# KX1_DB_PWR.net
KiCad netlist of a schematic drawn in Altium Designer
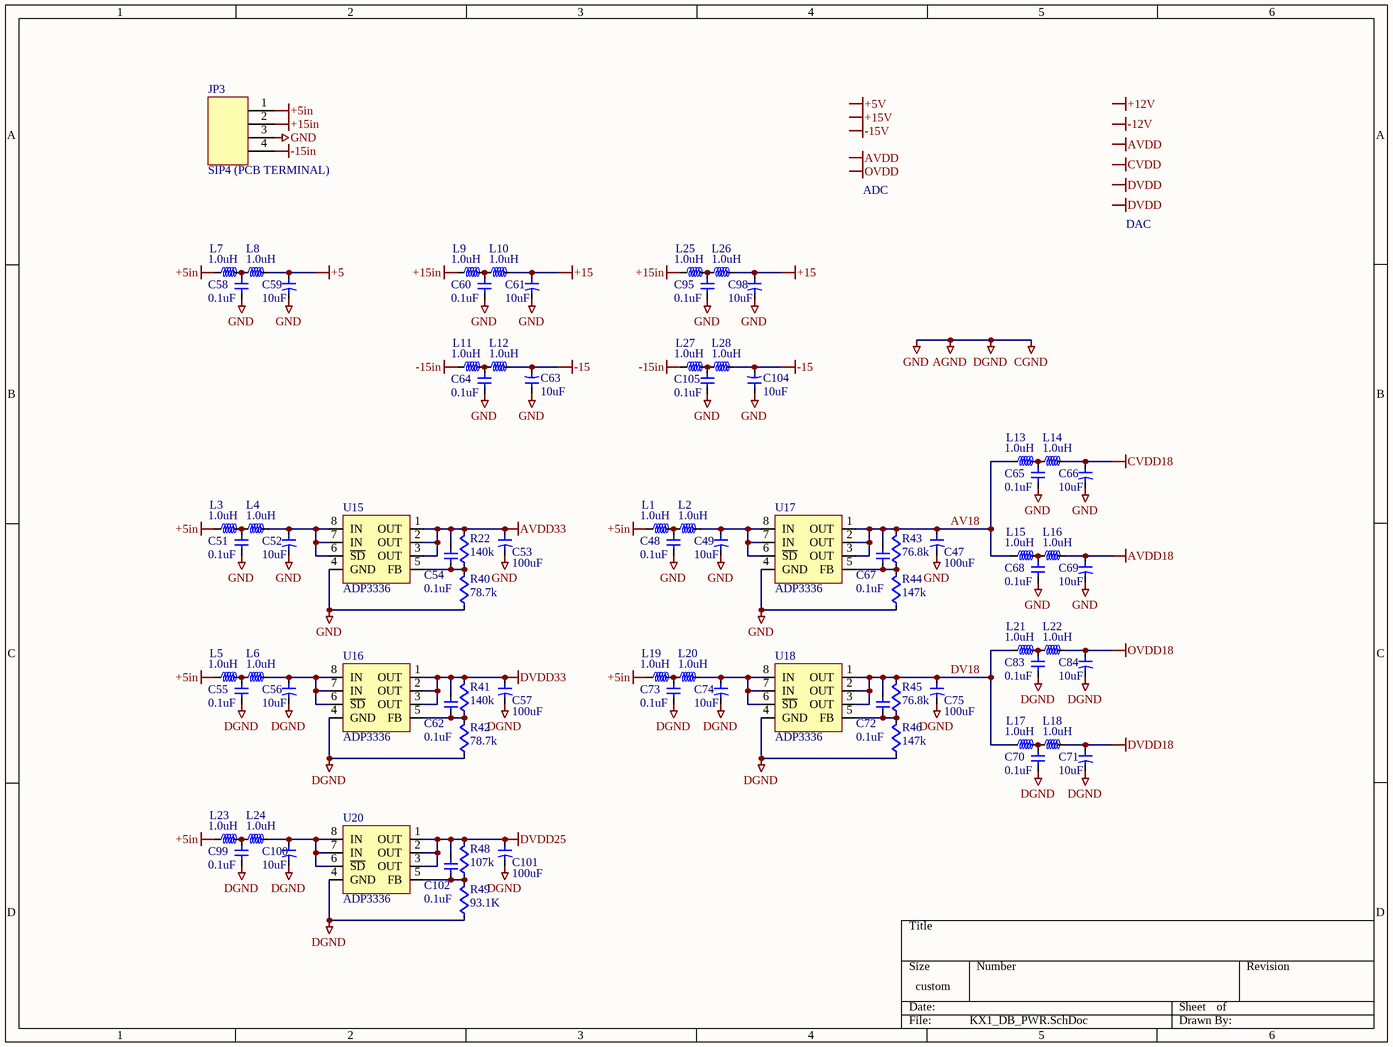
[diagram p0: KX1_DB_PWR.SchDoc]

(export (version "E")
  (design (tool "Eeschema 10.0.6"))
  (components
    (comp (ref "C47")
      (value "100uF")
      (footprint "1206")
      (description "capacitor")
      (fields
        (field (name "MANUFACTURER") "TDK Corporation")
        (field (name "MANUFACTURER PART NUMBER") "C3216X5R0J107M")
      )
      (libsource (lib "KX1_DB") (part "CAPACITOR_SM"))
    )
    (comp (ref "C48")
      (value "0.1uF")
      (footprint "0603w")
      (description "capacitor")
      (fields
        (field (name "MANUFACTURER") "Kemet")
        (field (name "MANUFACTURER PART NUMBER") "C0603C104K3RACTU")
      )
      (libsource (lib "KX1_DB") (part "CAP_SM"))
    )
    (comp (ref "C49")
      (value "10uF")
      (footprint "1206")
      (description "ELECTROLYTIC capacitor")
      (fields
        (field (name "MANUFACTURER") "Nichicon")
        (field (name "MANUFACTURER PART NUMBER") "F971C106MAA")
      )
      (libsource (lib "KX1_DB") (part "CAPACITOR_SM"))
    )
    (comp (ref "C51")
      (value "0.1uF")
      (footprint "0603w")
      (description "capacitor")
      (fields
        (field (name "MANUFACTURER") "Kemet")
        (field (name "MANUFACTURER PART NUMBER") "C0603C104K3RACTU")
      )
      (libsource (lib "KX1_DB") (part "CAP_SM"))
    )
    (comp (ref "C52")
      (value "10uF")
      (footprint "1206")
      (description "ELECTROLYTIC capacitor")
      (fields
        (field (name "MANUFACTURER") "Nichicon")
        (field (name "MANUFACTURER PART NUMBER") "F971C106MAA")
      )
      (libsource (lib "KX1_DB") (part "CAPACITOR_SM"))
    )
    (comp (ref "C53")
      (value "100uF")
      (footprint "1206")
      (description "capacitor")
      (fields
        (field (name "MANUFACTURER") "TDK Corporation")
        (field (name "MANUFACTURER PART NUMBER") "C3216X5R0J107M")
      )
      (libsource (lib "KX1_DB") (part "CAPACITOR_SM"))
    )
    (comp (ref "C54")
      (value "0.1uF")
      (footprint "0603w")
      (description "capacitor")
      (fields
        (field (name "MANUFACTURER") "Kemet")
        (field (name "MANUFACTURER PART NUMBER") "C0603C104K3RACTU")
      )
      (libsource (lib "KX1_DB") (part "CAP_SM"))
    )
    (comp (ref "C55")
      (value "0.1uF")
      (footprint "0603w")
      (description "capacitor")
      (fields
        (field (name "MANUFACTURER") "Kemet")
        (field (name "MANUFACTURER PART NUMBER") "C0603C104K3RACTU")
      )
      (libsource (lib "KX1_DB") (part "CAP_SM"))
    )
    (comp (ref "C56")
      (value "10uF")
      (footprint "1206")
      (description "ELECTROLYTIC capacitor")
      (fields
        (field (name "MANUFACTURER") "Nichicon")
        (field (name "MANUFACTURER PART NUMBER") "F971C106MAA")
      )
      (libsource (lib "KX1_DB") (part "CAPACITOR_SM"))
    )
    (comp (ref "C57")
      (value "100uF")
      (footprint "1206")
      (description "capacitor")
      (fields
        (field (name "MANUFACTURER") "TDK Corporation")
        (field (name "MANUFACTURER PART NUMBER") "C3216X5R0J107M")
      )
      (libsource (lib "KX1_DB") (part "CAPACITOR_SM"))
    )
    (comp (ref "C58")
      (value "0.1uF")
      (footprint "0603w")
      (description "capacitor")
      (fields
        (field (name "MANUFACTURER") "Kemet")
        (field (name "MANUFACTURER PART NUMBER") "C0603C104K3RACTU")
      )
      (libsource (lib "KX1_DB") (part "CAP_SM"))
    )
    (comp (ref "C59")
      (value "10uF")
      (footprint "1206")
      (description "ELECTROLYTIC capacitor")
      (fields
        (field (name "MANUFACTURER") "Nichicon")
        (field (name "MANUFACTURER PART NUMBER") "F971C106MAA")
      )
      (libsource (lib "KX1_DB") (part "CAPACITOR_SM"))
    )
    (comp (ref "C60")
      (value "0.1uF")
      (footprint "0603w")
      (description "capacitor")
      (fields
        (field (name "MANUFACTURER") "Kemet")
        (field (name "MANUFACTURER PART NUMBER") "C0603C104K3RACTU")
      )
      (libsource (lib "KX1_DB") (part "CAP_SM"))
    )
    (comp (ref "C61")
      (value "10uF")
      (footprint "1206")
      (description "ELECTROLYTIC capacitor")
      (fields
        (field (name "MANUFACTURER") "Nichicon")
        (field (name "MANUFACTURER PART NUMBER") "F971C106MAA")
      )
      (libsource (lib "KX1_DB") (part "CAPACITOR_SM"))
    )
    (comp (ref "C62")
      (value "0.1uF")
      (footprint "0603w")
      (description "capacitor")
      (fields
        (field (name "MANUFACTURER") "Kemet")
        (field (name "MANUFACTURER PART NUMBER") "C0603C104K3RACTU")
      )
      (libsource (lib "KX1_DB") (part "CAP_SM"))
    )
    (comp (ref "C63")
      (value "10uF")
      (footprint "1206")
      (description "ELECTROLYTIC capacitor")
      (fields
        (field (name "MANUFACTURER") "Nichicon")
        (field (name "MANUFACTURER PART NUMBER") "F971C106MAA")
      )
      (libsource (lib "KX1_DB") (part "CAPACITOR_SM"))
    )
    (comp (ref "C64")
      (value "0.1uF")
      (footprint "0603w")
      (description "capacitor")
      (fields
        (field (name "MANUFACTURER") "Kemet")
        (field (name "MANUFACTURER PART NUMBER") "C0603C104K3RACTU")
      )
      (libsource (lib "KX1_DB") (part "CAP_SM"))
    )
    (comp (ref "C65")
      (value "0.1uF")
      (footprint "0603w")
      (description "capacitor")
      (fields
        (field (name "MANUFACTURER") "Kemet")
        (field (name "MANUFACTURER PART NUMBER") "C0603C104K3RACTU")
      )
      (libsource (lib "KX1_DB") (part "CAP_SM"))
    )
    (comp (ref "C66")
      (value "10uF")
      (footprint "1206")
      (description "ELECTROLYTIC capacitor")
      (fields
        (field (name "MANUFACTURER") "Nichicon")
        (field (name "MANUFACTURER PART NUMBER") "F971C106MAA")
      )
      (libsource (lib "KX1_DB") (part "CAPACITOR_SM"))
    )
    (comp (ref "C67")
      (value "0.1uF")
      (footprint "0603w")
      (description "capacitor")
      (fields
        (field (name "MANUFACTURER") "Kemet")
        (field (name "MANUFACTURER PART NUMBER") "C0603C104K3RACTU")
      )
      (libsource (lib "KX1_DB") (part "CAP_SM"))
    )
    (comp (ref "C68")
      (value "0.1uF")
      (footprint "0603w")
      (description "capacitor")
      (fields
        (field (name "MANUFACTURER") "Kemet")
        (field (name "MANUFACTURER PART NUMBER") "C0603C104K3RACTU")
      )
      (libsource (lib "KX1_DB") (part "CAP_SM"))
    )
    (comp (ref "C69")
      (value "10uF")
      (footprint "1206")
      (description "ELECTROLYTIC capacitor")
      (fields
        (field (name "MANUFACTURER") "Nichicon")
        (field (name "MANUFACTURER PART NUMBER") "F971C106MAA")
      )
      (libsource (lib "KX1_DB") (part "CAPACITOR_SM"))
    )
    (comp (ref "C70")
      (value "0.1uF")
      (footprint "0603w")
      (description "capacitor")
      (fields
        (field (name "MANUFACTURER") "Kemet")
        (field (name "MANUFACTURER PART NUMBER") "C0603C104K3RACTU")
      )
      (libsource (lib "KX1_DB") (part "CAP_SM"))
    )
    (comp (ref "C71")
      (value "10uF")
      (footprint "1206")
      (description "ELECTROLYTIC capacitor")
      (fields
        (field (name "MANUFACTURER") "Nichicon")
        (field (name "MANUFACTURER PART NUMBER") "F971C106MAA")
      )
      (libsource (lib "KX1_DB") (part "CAPACITOR_SM"))
    )
    (comp (ref "C72")
      (value "0.1uF")
      (footprint "0603w")
      (description "capacitor")
      (fields
        (field (name "MANUFACTURER") "Kemet")
        (field (name "MANUFACTURER PART NUMBER") "C0603C104K3RACTU")
      )
      (libsource (lib "KX1_DB") (part "CAP_SM"))
    )
    (comp (ref "C73")
      (value "0.1uF")
      (footprint "0603w")
      (description "capacitor")
      (fields
        (field (name "MANUFACTURER") "Kemet")
        (field (name "MANUFACTURER PART NUMBER") "C0603C104K3RACTU")
      )
      (libsource (lib "KX1_DB") (part "CAP_SM"))
    )
    (comp (ref "C74")
      (value "10uF")
      (footprint "1206")
      (description "ELECTROLYTIC capacitor")
      (fields
        (field (name "MANUFACTURER") "Nichicon")
        (field (name "MANUFACTURER PART NUMBER") "F971C106MAA")
      )
      (libsource (lib "KX1_DB") (part "CAPACITOR_SM"))
    )
    (comp (ref "C75")
      (value "100uF")
      (footprint "1206")
      (description "capacitor")
      (fields
        (field (name "MANUFACTURER") "TDK Corporation")
        (field (name "MANUFACTURER PART NUMBER") "C3216X5R0J107M")
      )
      (libsource (lib "KX1_DB") (part "CAPACITOR_SM"))
    )
    (comp (ref "C83")
      (value "0.1uF")
      (footprint "0603w")
      (description "capacitor")
      (fields
        (field (name "MANUFACTURER") "Kemet")
        (field (name "MANUFACTURER PART NUMBER") "C0603C104K3RACTU")
      )
      (libsource (lib "KX1_DB") (part "CAP_SM"))
    )
    (comp (ref "C84")
      (value "10uF")
      (footprint "1206")
      (description "ELECTROLYTIC capacitor")
      (fields
        (field (name "MANUFACTURER") "Nichicon")
        (field (name "MANUFACTURER PART NUMBER") "F971C106MAA")
      )
      (libsource (lib "KX1_DB") (part "CAPACITOR_SM"))
    )
    (comp (ref "C95")
      (value "0.1uF")
      (footprint "0603w")
      (description "capacitor")
      (fields
        (field (name "MANUFACTURER") "Kemet")
        (field (name "MANUFACTURER PART NUMBER") "C0603C104K3RACTU")
      )
      (libsource (lib "KX1_DB") (part "CAP_SM"))
    )
    (comp (ref "C98")
      (value "10uF")
      (footprint "1206")
      (description "ELECTROLYTIC capacitor")
      (fields
        (field (name "MANUFACTURER") "Nichicon")
        (field (name "MANUFACTURER PART NUMBER") "F971C106MAA")
      )
      (libsource (lib "KX1_DB") (part "CAPACITOR_SM"))
    )
    (comp (ref "C99")
      (value "0.1uF")
      (footprint "0603w")
      (description "capacitor")
      (fields
        (field (name "MANUFACTURER") "Kemet")
        (field (name "MANUFACTURER PART NUMBER") "C0603C104K3RACTU")
      )
      (libsource (lib "KX1_DB") (part "CAP_SM"))
    )
    (comp (ref "C100")
      (value "10uF")
      (footprint "1206")
      (description "ELECTROLYTIC capacitor")
      (fields
        (field (name "MANUFACTURER") "Nichicon")
        (field (name "MANUFACTURER PART NUMBER") "F971C106MAA")
      )
      (libsource (lib "KX1_DB") (part "CAPACITOR_SM"))
    )
    (comp (ref "C101")
      (value "100uF")
      (footprint "1206")
      (description "capacitor")
      (fields
        (field (name "MANUFACTURER") "TDK Corporation")
        (field (name "MANUFACTURER PART NUMBER") "C3216X5R0J107M")
      )
      (libsource (lib "KX1_DB") (part "CAPACITOR_SM"))
    )
    (comp (ref "C102")
      (value "0.1uF")
      (footprint "0603w")
      (description "capacitor")
      (fields
        (field (name "MANUFACTURER") "Kemet")
        (field (name "MANUFACTURER PART NUMBER") "C0603C104K3RACTU")
      )
      (libsource (lib "KX1_DB") (part "CAP_SM"))
    )
    (comp (ref "C104")
      (value "10uF")
      (footprint "1206")
      (description "ELECTROLYTIC capacitor")
      (fields
        (field (name "MANUFACTURER") "Nichicon")
        (field (name "MANUFACTURER PART NUMBER") "F971C106MAA")
      )
      (libsource (lib "KX1_DB") (part "CAPACITOR_SM"))
    )
    (comp (ref "C105")
      (value "0.1uF")
      (footprint "0603w")
      (description "capacitor")
      (fields
        (field (name "MANUFACTURER") "Kemet")
        (field (name "MANUFACTURER PART NUMBER") "C0603C104K3RACTU")
      )
      (libsource (lib "KX1_DB") (part "CAP_SM"))
    )
    (comp (ref "JP3")
      (value "SIP4 (PCB TERMINAL)")
      (footprint "SIP4MOLEX")
      (description "4 pin molex connector")
      (fields
        (field (name "MANUFACTURER") "Molex Inc")
        (field (name "MANUFACTURER PART NUMBER") "22-29-2041")
      )
      (libsource (lib "KX1_DB") (part "SIP4 (PCB TERMINAL)"))
    )
    (comp (ref "L1")
      (value "1.0uH")
      (footprint "1210")
      (description "inductor")
      (fields
        (field (name "MANUFACTURER") "Murata Electronics North America")
        (field (name "MANUFACTURER PART NUMBER") "LQH32CN1R0M23L")
      )
      (libsource (lib "KX1_DB") (part "INDUCTOR_SM"))
    )
    (comp (ref "L2")
      (value "1.0uH")
      (footprint "1210")
      (description "inductor")
      (fields
        (field (name "MANUFACTURER") "Murata Electronics North America")
        (field (name "MANUFACTURER PART NUMBER") "LQH32CN1R0M23L")
      )
      (libsource (lib "KX1_DB") (part "INDUCTOR_SM"))
    )
    (comp (ref "L3")
      (value "1.0uH")
      (footprint "0805")
      (description "inductor")
      (fields
        (field (name "MANUFACTURER") "Murata Electronics North America")
        (field (name "MANUFACTURER PART NUMBER") "LQM21FN1R0N00D")
      )
      (libsource (lib "KX1_DB") (part "INDUCTOR_SM"))
    )
    (comp (ref "L4")
      (value "1.0uH")
      (footprint "0805")
      (description "inductor")
      (fields
        (field (name "MANUFACTURER") "Murata Electronics North America")
        (field (name "MANUFACTURER PART NUMBER") "LQM21FN1R0N00D")
      )
      (libsource (lib "KX1_DB") (part "INDUCTOR_SM"))
    )
    (comp (ref "L5")
      (value "1.0uH")
      (footprint "0805")
      (description "inductor")
      (fields
        (field (name "MANUFACTURER") "Murata Electronics North America")
        (field (name "MANUFACTURER PART NUMBER") "LQM21FN1R0N00D")
      )
      (libsource (lib "KX1_DB") (part "INDUCTOR_SM"))
    )
    (comp (ref "L6")
      (value "1.0uH")
      (footprint "0805")
      (description "inductor")
      (fields
        (field (name "MANUFACTURER") "Murata Electronics North America")
        (field (name "MANUFACTURER PART NUMBER") "LQM21FN1R0N00D")
      )
      (libsource (lib "KX1_DB") (part "INDUCTOR_SM"))
    )
    (comp (ref "L7")
      (value "1.0uH")
      (footprint "1210")
      (description "inductor")
      (fields
        (field (name "MANUFACTURER") "Murata Electronics North America")
        (field (name "MANUFACTURER PART NUMBER") "LQH32CN1R0M23L")
      )
      (libsource (lib "KX1_DB") (part "INDUCTOR_SM"))
    )
    (comp (ref "L8")
      (value "1.0uH")
      (footprint "1210")
      (description "inductor")
      (fields
        (field (name "MANUFACTURER") "Murata Electronics North America")
        (field (name "MANUFACTURER PART NUMBER") "LQH32CN1R0M23L")
      )
      (libsource (lib "KX1_DB") (part "INDUCTOR_SM"))
    )
    (comp (ref "L9")
      (value "1.0uH")
      (footprint "1210")
      (description "inductor")
      (fields
        (field (name "MANUFACTURER") "Murata Electronics North America")
        (field (name "MANUFACTURER PART NUMBER") "LQH32CN1R0M23L")
      )
      (libsource (lib "KX1_DB") (part "INDUCTOR_SM"))
    )
    (comp (ref "L10")
      (value "1.0uH")
      (footprint "1210")
      (description "inductor")
      (fields
        (field (name "MANUFACTURER") "Murata Electronics North America")
        (field (name "MANUFACTURER PART NUMBER") "LQH32CN1R0M23L")
      )
      (libsource (lib "KX1_DB") (part "INDUCTOR_SM"))
    )
    (comp (ref "L11")
      (value "1.0uH")
      (footprint "1210")
      (description "inductor")
      (fields
        (field (name "MANUFACTURER") "Murata Electronics North America")
        (field (name "MANUFACTURER PART NUMBER") "LQH32CN1R0M23L")
      )
      (libsource (lib "KX1_DB") (part "INDUCTOR_SM"))
    )
    (comp (ref "L12")
      (value "1.0uH")
      (footprint "1210")
      (description "inductor")
      (fields
        (field (name "MANUFACTURER") "Murata Electronics North America")
        (field (name "MANUFACTURER PART NUMBER") "LQH32CN1R0M23L")
      )
      (libsource (lib "KX1_DB") (part "INDUCTOR_SM"))
    )
    (comp (ref "L13")
      (value "1.0uH")
      (footprint "0805")
      (description "inductor")
      (fields
        (field (name "MANUFACTURER") "Murata Electronics North America")
        (field (name "MANUFACTURER PART NUMBER") "LQM21FN1R0N00D")
      )
      (libsource (lib "KX1_DB") (part "INDUCTOR_SM"))
    )
    (comp (ref "L14")
      (value "1.0uH")
      (footprint "0805")
      (description "inductor")
      (fields
        (field (name "MANUFACTURER") "Murata Electronics North America")
        (field (name "MANUFACTURER PART NUMBER") "LQM21FN1R0N00D")
      )
      (libsource (lib "KX1_DB") (part "INDUCTOR_SM"))
    )
    (comp (ref "L15")
      (value "1.0uH")
      (footprint "1210")
      (description "inductor")
      (fields
        (field (name "MANUFACTURER") "Murata Electronics North America")
        (field (name "MANUFACTURER PART NUMBER") "LQH32CN1R0M23L")
      )
      (libsource (lib "KX1_DB") (part "INDUCTOR_SM"))
    )
    (comp (ref "L16")
      (value "1.0uH")
      (footprint "1210")
      (description "inductor")
      (fields
        (field (name "MANUFACTURER") "Murata Electronics North America")
        (field (name "MANUFACTURER PART NUMBER") "LQH32CN1R0M23L")
      )
      (libsource (lib "KX1_DB") (part "INDUCTOR_SM"))
    )
    (comp (ref "L17")
      (value "1.0uH")
      (footprint "0805")
      (description "inductor")
      (fields
        (field (name "MANUFACTURER") "Murata Electronics North America")
        (field (name "MANUFACTURER PART NUMBER") "LQM21FN1R0N00D")
      )
      (libsource (lib "KX1_DB") (part "INDUCTOR_SM"))
    )
    (comp (ref "L18")
      (value "1.0uH")
      (footprint "0805")
      (description "inductor")
      (fields
        (field (name "MANUFACTURER") "Murata Electronics North America")
        (field (name "MANUFACTURER PART NUMBER") "LQM21FN1R0N00D")
      )
      (libsource (lib "KX1_DB") (part "INDUCTOR_SM"))
    )
    (comp (ref "L19")
      (value "1.0uH")
      (footprint "0805")
      (description "inductor")
      (fields
        (field (name "MANUFACTURER") "Murata Electronics North America")
        (field (name "MANUFACTURER PART NUMBER") "LQM21FN1R0N00D")
      )
      (libsource (lib "KX1_DB") (part "INDUCTOR_SM"))
    )
    (comp (ref "L20")
      (value "1.0uH")
      (footprint "0805")
      (description "inductor")
      (fields
        (field (name "MANUFACTURER") "Murata Electronics North America")
        (field (name "MANUFACTURER PART NUMBER") "LQM21FN1R0N00D")
      )
      (libsource (lib "KX1_DB") (part "INDUCTOR_SM"))
    )
    (comp (ref "L21")
      (value "1.0uH")
      (footprint "0805")
      (description "inductor")
      (fields
        (field (name "MANUFACTURER") "Murata Electronics North America")
        (field (name "MANUFACTURER PART NUMBER") "LQM21FN1R0N00D")
      )
      (libsource (lib "KX1_DB") (part "INDUCTOR_SM"))
    )
    (comp (ref "L22")
      (value "1.0uH")
      (footprint "0805")
      (description "inductor")
      (fields
        (field (name "MANUFACTURER") "Murata Electronics North America")
        (field (name "MANUFACTURER PART NUMBER") "LQM21FN1R0N00D")
      )
      (libsource (lib "KX1_DB") (part "INDUCTOR_SM"))
    )
    (comp (ref "L23")
      (value "1.0uH")
      (footprint "0805")
      (description "inductor")
      (fields
        (field (name "MANUFACTURER") "Murata Electronics North America")
        (field (name "MANUFACTURER PART NUMBER") "LQM21FN1R0N00D")
      )
      (libsource (lib "KX1_DB") (part "INDUCTOR_SM"))
    )
    (comp (ref "L24")
      (value "1.0uH")
      (footprint "0805")
      (description "inductor")
      (fields
        (field (name "MANUFACTURER") "Murata Electronics North America")
        (field (name "MANUFACTURER PART NUMBER") "LQM21FN1R0N00D")
      )
      (libsource (lib "KX1_DB") (part "INDUCTOR_SM"))
    )
    (comp (ref "L25")
      (value "1.0uH")
      (footprint "1210")
      (description "inductor")
      (fields
        (field (name "MANUFACTURER") "Murata Electronics North America")
        (field (name "MANUFACTURER PART NUMBER") "LQH32CN1R0M23L")
      )
      (libsource (lib "KX1_DB") (part "INDUCTOR_SM"))
    )
    (comp (ref "L26")
      (value "1.0uH")
      (footprint "1210")
      (description "inductor")
      (fields
        (field (name "MANUFACTURER") "Murata Electronics North America")
        (field (name "MANUFACTURER PART NUMBER") "LQH32CN1R0M23L")
      )
      (libsource (lib "KX1_DB") (part "INDUCTOR_SM"))
    )
    (comp (ref "L27")
      (value "1.0uH")
      (footprint "1210")
      (description "inductor")
      (fields
        (field (name "MANUFACTURER") "Murata Electronics North America")
        (field (name "MANUFACTURER PART NUMBER") "LQH32CN1R0M23L")
      )
      (libsource (lib "KX1_DB") (part "INDUCTOR_SM"))
    )
    (comp (ref "L28")
      (value "1.0uH")
      (footprint "1210")
      (description "inductor")
      (fields
        (field (name "MANUFACTURER") "Murata Electronics North America")
        (field (name "MANUFACTURER PART NUMBER") "LQH32CN1R0M23L")
      )
      (libsource (lib "KX1_DB") (part "INDUCTOR_SM"))
    )
    (comp (ref "R22")
      (value "140k")
      (footprint "0603w")
      (description "resistor")
      (fields
        (field (name "MANUFACTURER") "Yageo")
        (field (name "MANUFACTURER PART NUMBER") "RC0603FR-07140KL")
      )
      (libsource (lib "KX1_DB") (part "RES_SM"))
    )
    (comp (ref "R40")
      (value "78.7k")
      (footprint "0603w")
      (description "resistor")
      (fields
        (field (name "MANUFACTURER") "Yageo")
        (field (name "MANUFACTURER PART NUMBER") "RC0603FR-0778K7L")
      )
      (libsource (lib "KX1_DB") (part "RES_SM"))
    )
    (comp (ref "R41")
      (value "140k")
      (footprint "0603w")
      (description "resistor")
      (fields
        (field (name "MANUFACTURER") "Yageo")
        (field (name "MANUFACTURER PART NUMBER") "RC0603FR-07140KL")
      )
      (libsource (lib "KX1_DB") (part "RES_SM"))
    )
    (comp (ref "R42")
      (value "78.7k")
      (footprint "0603w")
      (description "resistor")
      (fields
        (field (name "MANUFACTURER") "Yageo")
        (field (name "MANUFACTURER PART NUMBER") "RC0603FR-0778K7L")
      )
      (libsource (lib "KX1_DB") (part "RES_SM"))
    )
    (comp (ref "R43")
      (value "76.8k")
      (footprint "0603w")
      (description "resistor")
      (fields
        (field (name "MANUFACTURER") "Yageo")
        (field (name "MANUFACTURER PART NUMBER") "RC0603FR-0776K8L")
      )
      (libsource (lib "KX1_DB") (part "RES_SM"))
    )
    (comp (ref "R44")
      (value "147k")
      (footprint "0603w")
      (description "resistor")
      (fields
        (field (name "MANUFACTURER") "Yageo")
        (field (name "MANUFACTURER PART NUMBER") "RC0603FR-07147KL")
      )
      (libsource (lib "KX1_DB") (part "RES_SM"))
    )
    (comp (ref "R45")
      (value "76.8k")
      (footprint "0603w")
      (description "resistor")
      (fields
        (field (name "MANUFACTURER") "Yageo")
        (field (name "MANUFACTURER PART NUMBER") "RC0603FR-0776K8L")
      )
      (libsource (lib "KX1_DB") (part "RES_SM"))
    )
    (comp (ref "R46")
      (value "147k")
      (footprint "0603w")
      (description "resistor")
      (fields
        (field (name "MANUFACTURER") "Yageo")
        (field (name "MANUFACTURER PART NUMBER") "RC0603FR-07147KL")
      )
      (libsource (lib "KX1_DB") (part "RES_SM"))
    )
    (comp (ref "R48")
      (value "107k")
      (footprint "0603w")
      (description "resistor")
      (fields
        (field (name "MANUFACTURER") "Yageo")
        (field (name "MANUFACTURER PART NUMBER") "RC0603FR-07107KL")
      )
      (libsource (lib "KX1_DB") (part "RES_SM"))
    )
    (comp (ref "R49")
      (value "93.1K")
      (footprint "0603w")
      (description "resistor")
      (fields
        (field (name "MANUFACTURER") "Yageo")
        (field (name "MANUFACTURER PART NUMBER") "RC0603FR-0793K1L")
      )
      (libsource (lib "KX1_DB") (part "RES_SM"))
    )
    (comp (ref "U15")
      (value "ADP3336")
      (footprint "MSOP08")
      (description "regulator")
      (fields
        (field (name "MANUFACTURER") "Analog Devices Inc")
        (field (name "MANUFACTURER PART NUMBER") "ADP3336ARMZ-REEL7")
      )
      (libsource (lib "KX1_DB") (part "ADP3336"))
    )
    (comp (ref "U16")
      (value "ADP3336")
      (footprint "MSOP08")
      (description "regulator")
      (fields
        (field (name "MANUFACTURER") "Analog Devices Inc")
        (field (name "MANUFACTURER PART NUMBER") "ADP3336ARMZ-REEL7")
      )
      (libsource (lib "KX1_DB") (part "ADP3336"))
    )
    (comp (ref "U17")
      (value "ADP3336")
      (footprint "MSOP08")
      (description "regulator")
      (fields
        (field (name "MANUFACTURER") "Analog Devices Inc")
        (field (name "MANUFACTURER PART NUMBER") "ADP3336ARMZ-REEL7")
      )
      (libsource (lib "KX1_DB") (part "ADP3336"))
    )
    (comp (ref "U18")
      (value "ADP3336")
      (footprint "MSOP08")
      (description "regulator")
      (fields
        (field (name "MANUFACTURER") "Analog Devices Inc")
        (field (name "MANUFACTURER PART NUMBER") "ADP3336ARMZ-REEL7")
      )
      (libsource (lib "KX1_DB") (part "ADP3336"))
    )
    (comp (ref "U20")
      (value "ADP3336")
      (footprint "MSOP08")
      (description "regulator")
      (fields
        (field (name "MANUFACTURER") "Analog Devices Inc")
        (field (name "MANUFACTURER PART NUMBER") "ADP3336ARMZ-REEL7")
      )
      (libsource (lib "KX1_DB") (part "ADP3336"))
    )
  )
  (nets
    (net (code "1") (name "+5") (class "Default")
      (node (ref "C59") (pin "1") (pintype "passive"))
      (node (ref "L8") (pin "2") (pintype "passive"))
    )
    (net (code "3") (name "+5in") (class "Default")
      (node (ref "JP3") (pin "1") (pintype "passive"))
      (node (ref "L1") (pin "1") (pintype "passive"))
      (node (ref "L19") (pin "1") (pintype "passive"))
      (node (ref "L23") (pin "1") (pintype "passive"))
      (node (ref "L3") (pin "1") (pintype "passive"))
      (node (ref "L5") (pin "1") (pintype "passive"))
      (node (ref "L7") (pin "1") (pintype "passive"))
    )
    (net (code "5") (name "+15") (class "Default")
      (node (ref "C61") (pin "1") (pintype "passive"))
      (node (ref "C98") (pin "1") (pintype "passive"))
      (node (ref "L10") (pin "2") (pintype "passive"))
      (node (ref "L26") (pin "2") (pintype "passive"))
    )
    (net (code "7") (name "+15in") (class "Default")
      (node (ref "JP3") (pin "2") (pintype "passive"))
      (node (ref "L25") (pin "1") (pintype "passive"))
      (node (ref "L9") (pin "1") (pintype "passive"))
    )
    (net (code "9") (name "-15") (class "Default")
      (node (ref "C104") (pin "2") (pintype "passive"))
      (node (ref "C63") (pin "2") (pintype "passive"))
      (node (ref "L12") (pin "2") (pintype "passive"))
      (node (ref "L28") (pin "2") (pintype "passive"))
    )
    (net (code "11") (name "-15in") (class "Default")
      (node (ref "JP3") (pin "4") (pintype "passive"))
      (node (ref "L11") (pin "1") (pintype "passive"))
      (node (ref "L27") (pin "1") (pintype "passive"))
    )
    (net (code "12") (name "/AV18") (class "Default")
      (node (ref "C47") (pin "1") (pintype "passive"))
      (node (ref "C67") (pin "1") (pintype "passive"))
      (node (ref "L13") (pin "1") (pintype "passive"))
      (node (ref "L15") (pin "1") (pintype "passive"))
      (node (ref "R43") (pin "2") (pintype "passive"))
      (node (ref "U17") (pin "1") (pinfunction "OUT_1") (pintype "passive"))
      (node (ref "U17") (pin "2") (pinfunction "OUT_2") (pintype "passive"))
      (node (ref "U17") (pin "3") (pinfunction "OUT_3") (pintype "passive"))
    )
    (net (code "13") (name "/DV18") (class "Default")
      (node (ref "C72") (pin "1") (pintype "passive"))
      (node (ref "C75") (pin "1") (pintype "passive"))
      (node (ref "L17") (pin "1") (pintype "passive"))
      (node (ref "L21") (pin "1") (pintype "passive"))
      (node (ref "R45") (pin "2") (pintype "passive"))
      (node (ref "U18") (pin "1") (pinfunction "OUT_1") (pintype "passive"))
      (node (ref "U18") (pin "2") (pinfunction "OUT_2") (pintype "passive"))
      (node (ref "U18") (pin "3") (pinfunction "OUT_3") (pintype "passive"))
    )
    (net (code "14") (name "AGND") (class "Default")
      (node (ref "C100") (pin "2") (pintype "passive"))
      (node (ref "C101") (pin "2") (pintype "passive"))
      (node (ref "C104") (pin "1") (pintype "passive"))
      (node (ref "C105") (pin "2") (pintype "passive"))
      (node (ref "C47") (pin "2") (pintype "passive"))
      (node (ref "C48") (pin "2") (pintype "passive"))
      (node (ref "C49") (pin "2") (pintype "passive"))
      (node (ref "C51") (pin "2") (pintype "passive"))
      (node (ref "C52") (pin "2") (pintype "passive"))
      (node (ref "C53") (pin "2") (pintype "passive"))
      (node (ref "C55") (pin "2") (pintype "passive"))
      (node (ref "C56") (pin "2") (pintype "passive"))
      (node (ref "C57") (pin "2") (pintype "passive"))
      (node (ref "C58") (pin "2") (pintype "passive"))
      (node (ref "C59") (pin "2") (pintype "passive"))
      (node (ref "C60") (pin "2") (pintype "passive"))
      (node (ref "C61") (pin "2") (pintype "passive"))
      (node (ref "C63") (pin "1") (pintype "passive"))
      (node (ref "C64") (pin "2") (pintype "passive"))
      (node (ref "C65") (pin "2") (pintype "passive"))
      (node (ref "C66") (pin "2") (pintype "passive"))
      (node (ref "C68") (pin "2") (pintype "passive"))
      (node (ref "C69") (pin "2") (pintype "passive"))
      (node (ref "C70") (pin "2") (pintype "passive"))
      (node (ref "C71") (pin "2") (pintype "passive"))
      (node (ref "C73") (pin "2") (pintype "passive"))
      (node (ref "C74") (pin "2") (pintype "passive"))
      (node (ref "C75") (pin "2") (pintype "passive"))
      (node (ref "C83") (pin "2") (pintype "passive"))
      (node (ref "C84") (pin "2") (pintype "passive"))
      (node (ref "C95") (pin "2") (pintype "passive"))
      (node (ref "C98") (pin "2") (pintype "passive"))
      (node (ref "C99") (pin "2") (pintype "passive"))
      (node (ref "JP3") (pin "3") (pintype "passive"))
      (node (ref "R40") (pin "1") (pintype "passive"))
      (node (ref "R42") (pin "1") (pintype "passive"))
      (node (ref "R44") (pin "1") (pintype "passive"))
      (node (ref "R46") (pin "1") (pintype "passive"))
      (node (ref "R49") (pin "1") (pintype "passive"))
      (node (ref "U15") (pin "4") (pinfunction "GND_4") (pintype "passive"))
      (node (ref "U16") (pin "4") (pinfunction "GND_4") (pintype "passive"))
      (node (ref "U17") (pin "4") (pinfunction "GND_4") (pintype "passive"))
      (node (ref "U18") (pin "4") (pinfunction "GND_4") (pintype "passive"))
      (node (ref "U20") (pin "4") (pinfunction "GND_4") (pintype "passive"))
    )
    (net (code "16") (name "AVDD18") (class "Default")
      (node (ref "C69") (pin "1") (pintype "passive"))
      (node (ref "L16") (pin "2") (pintype "passive"))
    )
    (net (code "17") (name "AVDD33") (class "Default")
      (node (ref "C53") (pin "1") (pintype "passive"))
      (node (ref "C54") (pin "1") (pintype "passive"))
      (node (ref "R22") (pin "2") (pintype "passive"))
      (node (ref "U15") (pin "1") (pinfunction "OUT_1") (pintype "passive"))
      (node (ref "U15") (pin "2") (pinfunction "OUT_2") (pintype "passive"))
      (node (ref "U15") (pin "3") (pinfunction "OUT_3") (pintype "passive"))
    )
    (net (code "19") (name "CVDD18") (class "Default")
      (node (ref "C66") (pin "1") (pintype "passive"))
      (node (ref "L14") (pin "2") (pintype "passive"))
    )
    (net (code "21") (name "DVDD18") (class "Default")
      (node (ref "C71") (pin "1") (pintype "passive"))
      (node (ref "L18") (pin "2") (pintype "passive"))
    )
    (net (code "22") (name "DVDD25") (class "Default")
      (node (ref "C101") (pin "1") (pintype "passive"))
      (node (ref "C102") (pin "1") (pintype "passive"))
      (node (ref "R48") (pin "2") (pintype "passive"))
      (node (ref "U20") (pin "1") (pinfunction "OUT_1") (pintype "passive"))
      (node (ref "U20") (pin "2") (pinfunction "OUT_2") (pintype "passive"))
      (node (ref "U20") (pin "3") (pinfunction "OUT_3") (pintype "passive"))
    )
    (net (code "23") (name "DVDD33") (class "Default")
      (node (ref "C57") (pin "1") (pintype "passive"))
      (node (ref "C62") (pin "1") (pintype "passive"))
      (node (ref "R41") (pin "2") (pintype "passive"))
      (node (ref "U16") (pin "1") (pinfunction "OUT_1") (pintype "passive"))
      (node (ref "U16") (pin "2") (pinfunction "OUT_2") (pintype "passive"))
      (node (ref "U16") (pin "3") (pinfunction "OUT_3") (pintype "passive"))
    )
    (net (code "24") (name "Net-(C48-Pad1)") (class "Default")
      (node (ref "C48") (pin "1") (pintype "passive"))
      (node (ref "L1") (pin "2") (pintype "passive"))
      (node (ref "L2") (pin "1") (pintype "passive"))
    )
    (net (code "25") (name "Net-(C51-Pad1)") (class "Default")
      (node (ref "C51") (pin "1") (pintype "passive"))
      (node (ref "L3") (pin "2") (pintype "passive"))
      (node (ref "L4") (pin "1") (pintype "passive"))
    )
    (net (code "26") (name "Net-(C55-Pad1)") (class "Default")
      (node (ref "C55") (pin "1") (pintype "passive"))
      (node (ref "L5") (pin "2") (pintype "passive"))
      (node (ref "L6") (pin "1") (pintype "passive"))
    )
    (net (code "27") (name "Net-(C58-Pad1)") (class "Default")
      (node (ref "C58") (pin "1") (pintype "passive"))
      (node (ref "L7") (pin "2") (pintype "passive"))
      (node (ref "L8") (pin "1") (pintype "passive"))
    )
    (net (code "28") (name "Net-(C60-Pad1)") (class "Default")
      (node (ref "C60") (pin "1") (pintype "passive"))
      (node (ref "L10") (pin "1") (pintype "passive"))
      (node (ref "L9") (pin "2") (pintype "passive"))
    )
    (net (code "29") (name "Net-(C64-Pad1)") (class "Default")
      (node (ref "C64") (pin "1") (pintype "passive"))
      (node (ref "L11") (pin "2") (pintype "passive"))
      (node (ref "L12") (pin "1") (pintype "passive"))
    )
    (net (code "30") (name "Net-(C65-Pad1)") (class "Default")
      (node (ref "C65") (pin "1") (pintype "passive"))
      (node (ref "L13") (pin "2") (pintype "passive"))
      (node (ref "L14") (pin "1") (pintype "passive"))
    )
    (net (code "31") (name "Net-(C68-Pad1)") (class "Default")
      (node (ref "C68") (pin "1") (pintype "passive"))
      (node (ref "L15") (pin "2") (pintype "passive"))
      (node (ref "L16") (pin "1") (pintype "passive"))
    )
    (net (code "32") (name "Net-(C70-Pad1)") (class "Default")
      (node (ref "C70") (pin "1") (pintype "passive"))
      (node (ref "L17") (pin "2") (pintype "passive"))
      (node (ref "L18") (pin "1") (pintype "passive"))
    )
    (net (code "33") (name "Net-(C73-Pad1)") (class "Default")
      (node (ref "C73") (pin "1") (pintype "passive"))
      (node (ref "L19") (pin "2") (pintype "passive"))
      (node (ref "L20") (pin "1") (pintype "passive"))
    )
    (net (code "34") (name "Net-(C83-Pad1)") (class "Default")
      (node (ref "C83") (pin "1") (pintype "passive"))
      (node (ref "L21") (pin "2") (pintype "passive"))
      (node (ref "L22") (pin "1") (pintype "passive"))
    )
    (net (code "35") (name "Net-(C95-Pad1)") (class "Default")
      (node (ref "C95") (pin "1") (pintype "passive"))
      (node (ref "L25") (pin "2") (pintype "passive"))
      (node (ref "L26") (pin "1") (pintype "passive"))
    )
    (net (code "36") (name "Net-(C99-Pad1)") (class "Default")
      (node (ref "C99") (pin "1") (pintype "passive"))
      (node (ref "L23") (pin "2") (pintype "passive"))
      (node (ref "L24") (pin "1") (pintype "passive"))
    )
    (net (code "37") (name "Net-(C105-Pad1)") (class "Default")
      (node (ref "C105") (pin "1") (pintype "passive"))
      (node (ref "L27") (pin "2") (pintype "passive"))
      (node (ref "L28") (pin "1") (pintype "passive"))
    )
    (net (code "38") (name "Net-(U15-FB)") (class "Default")
      (node (ref "C54") (pin "2") (pintype "passive"))
      (node (ref "R22") (pin "1") (pintype "passive"))
      (node (ref "R40") (pin "2") (pintype "passive"))
      (node (ref "U15") (pin "5") (pinfunction "FB_5") (pintype "passive"))
    )
    (net (code "39") (name "Net-(U15-~{SD})") (class "Default")
      (node (ref "C52") (pin "1") (pintype "passive"))
      (node (ref "L4") (pin "2") (pintype "passive"))
      (node (ref "U15") (pin "6") (pinfunction "~{SD}_6") (pintype "passive"))
      (node (ref "U15") (pin "7") (pinfunction "IN_7") (pintype "passive"))
      (node (ref "U15") (pin "8") (pinfunction "IN_8") (pintype "passive"))
    )
    (net (code "40") (name "Net-(U16-FB)") (class "Default")
      (node (ref "C62") (pin "2") (pintype "passive"))
      (node (ref "R41") (pin "1") (pintype "passive"))
      (node (ref "R42") (pin "2") (pintype "passive"))
      (node (ref "U16") (pin "5") (pinfunction "FB_5") (pintype "passive"))
    )
    (net (code "41") (name "Net-(U16-~{SD})") (class "Default")
      (node (ref "C56") (pin "1") (pintype "passive"))
      (node (ref "L6") (pin "2") (pintype "passive"))
      (node (ref "U16") (pin "6") (pinfunction "~{SD}_6") (pintype "passive"))
      (node (ref "U16") (pin "7") (pinfunction "IN_7") (pintype "passive"))
      (node (ref "U16") (pin "8") (pinfunction "IN_8") (pintype "passive"))
    )
    (net (code "42") (name "Net-(U17-FB)") (class "Default")
      (node (ref "C67") (pin "2") (pintype "passive"))
      (node (ref "R43") (pin "1") (pintype "passive"))
      (node (ref "R44") (pin "2") (pintype "passive"))
      (node (ref "U17") (pin "5") (pinfunction "FB_5") (pintype "passive"))
    )
    (net (code "43") (name "Net-(U17-~{SD})") (class "Default")
      (node (ref "C49") (pin "1") (pintype "passive"))
      (node (ref "L2") (pin "2") (pintype "passive"))
      (node (ref "U17") (pin "6") (pinfunction "~{SD}_6") (pintype "passive"))
      (node (ref "U17") (pin "7") (pinfunction "IN_7") (pintype "passive"))
      (node (ref "U17") (pin "8") (pinfunction "IN_8") (pintype "passive"))
    )
    (net (code "44") (name "Net-(U18-FB)") (class "Default")
      (node (ref "C72") (pin "2") (pintype "passive"))
      (node (ref "R45") (pin "1") (pintype "passive"))
      (node (ref "R46") (pin "2") (pintype "passive"))
      (node (ref "U18") (pin "5") (pinfunction "FB_5") (pintype "passive"))
    )
    (net (code "45") (name "Net-(U18-~{SD})") (class "Default")
      (node (ref "C74") (pin "1") (pintype "passive"))
      (node (ref "L20") (pin "2") (pintype "passive"))
      (node (ref "U18") (pin "6") (pinfunction "~{SD}_6") (pintype "passive"))
      (node (ref "U18") (pin "7") (pinfunction "IN_7") (pintype "passive"))
      (node (ref "U18") (pin "8") (pinfunction "IN_8") (pintype "passive"))
    )
    (net (code "46") (name "Net-(U20-FB)") (class "Default")
      (node (ref "C102") (pin "2") (pintype "passive"))
      (node (ref "R48") (pin "1") (pintype "passive"))
      (node (ref "R49") (pin "2") (pintype "passive"))
      (node (ref "U20") (pin "5") (pinfunction "FB_5") (pintype "passive"))
    )
    (net (code "47") (name "Net-(U20-~{SD})") (class "Default")
      (node (ref "C100") (pin "1") (pintype "passive"))
      (node (ref "L24") (pin "2") (pintype "passive"))
      (node (ref "U20") (pin "6") (pinfunction "~{SD}_6") (pintype "passive"))
      (node (ref "U20") (pin "7") (pinfunction "IN_7") (pintype "passive"))
      (node (ref "U20") (pin "8") (pinfunction "IN_8") (pintype "passive"))
    )
    (net (code "49") (name "OVDD18") (class "Default")
      (node (ref "C84") (pin "1") (pintype "passive"))
      (node (ref "L22") (pin "2") (pintype "passive"))
    )
  )
)
